# relay_blk.net
KiCad netlist of a schematic drawn in Altium Designer
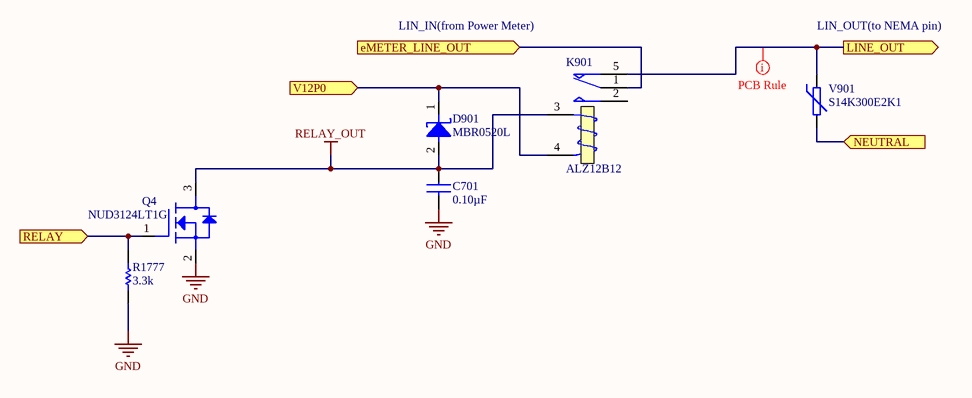
[diagram p0: relay_blk.SchDoc]

(export (version "E")
  (design (tool "Eeschema 10.0.6"))
  (components
    (comp (ref "C701")
      (value "0.10µF")
      (footprint "C0402")
      (description "CAP CER 0.1UF 50V X7R 0402")
      (fields (field (name "MPN") "GRM155R71H104ME14D"))
      (libsource (lib "Capacitor") (part "GRM155R71H104ME14D"))
    )
    (comp (ref "D901")
      (value "MBR0520L")
      (footprint "SOD123")
      (description "DIODE SCHOTTKY 20V 0.5A SOD123")
      (fields (field (name "MPN") "MBR0520L"))
      (libsource (lib "Diode") (part "MBR0520L"))
    )
    (comp (ref "K901")
      (value "ALZ12B12")
      (footprint "ALZ12B12 (custom)")
      (description "General Purpose Relays 16A 12VDC SPDT CLASS B")
      (fields (field (name "MPN") "ALZ12B12"))
      (libsource (lib "Relay") (part "ALZ12B12"))
    )
    (comp (ref "Q4")
      (value "NUD3124LT1G")
      (footprint "SOT-23-3")
      (description "IC INDCT LOAD DRVR AUTO SOT23")
      (fields (field (name "MPN") "NUD3124LT1G"))
      (libsource (lib "WiLamp") (part "NUD3124LT1G"))
    )
    (comp (ref "R1777")
      (value "3.3k")
      (footprint "R0402")
      (description "RES SMD 3.3K OHM 1% 1/16W 0402")
      (fields (field (name "MPN") "CRCW04023K30FKED"))
      (libsource (lib "Res") (part "CRCW04023K30FKED"))
    )
    (comp (ref "V901")
      (value "S14K300E2K1")
      (footprint "S14K300E2K1")
      (description "VARISTOR 470V 6KA DISC 14MM")
      (fields (field (name "MPN") "S14K300E2K1"))
      (libsource (lib "Varistor") (part "S14K300E2K1"))
    )
  )
  (nets
    (net (code "1") (name "/LINE_OUT") (class "Default")
      (node (ref "K901") (pin "5") (pinfunction "NC_5") (pintype "passive"))
      (node (ref "V901") (pin "2") (pinfunction "2_2") (pintype "passive"))
    )
    (net (code "2") (name "/NEUTRAL") (class "Default")
      (node (ref "V901") (pin "1") (pinfunction "1_1") (pintype "passive"))
    )
    (net (code "3") (name "/RELAY") (class "Default")
      (node (ref "Q4") (pin "1") (pinfunction "gate_1") (pintype "passive"))
      (node (ref "R1777") (pin "2") (pinfunction "2_2") (pintype "passive"))
    )
    (net (code "4") (name "/V12P0") (class "Default")
      (node (ref "D901") (pin "1") (pinfunction "cathode_1") (pintype "passive"))
      (node (ref "K901") (pin "4") (pinfunction "T2_4") (pintype "passive"))
    )
    (net (code "5") (name "/eMETER_LINE_OUT") (class "Default")
      (node (ref "K901") (pin "1") (pinfunction "COM_1") (pintype "passive"))
    )
    (net (code "6") (name "GND") (class "Default")
      (node (ref "C701") (pin "2") (pinfunction "2_2") (pintype "passive"))
      (node (ref "Q4") (pin "2") (pinfunction "source_2") (pintype "passive"))
      (node (ref "R1777") (pin "1") (pinfunction "1_1") (pintype "passive"))
    )
    (net (code "7") (name "RELAY_OUT") (class "Default")
      (node (ref "C701") (pin "1") (pinfunction "1_1") (pintype "passive"))
      (node (ref "D901") (pin "2") (pinfunction "anode_2") (pintype "passive"))
      (node (ref "K901") (pin "3") (pinfunction "T1_3") (pintype "passive"))
      (node (ref "Q4") (pin "3") (pinfunction "drain_3") (pintype "passive"))
    )
    (net (code "8") (name "unconnected-(K901-NO-Pad2)") (class "Default")
      (node (ref "K901") (pin "2") (pinfunction "NO_2") (pintype "passive"))
    )
  )
)
